# esp_car.net
KiCad netlist of a schematic drawn in EAGLE
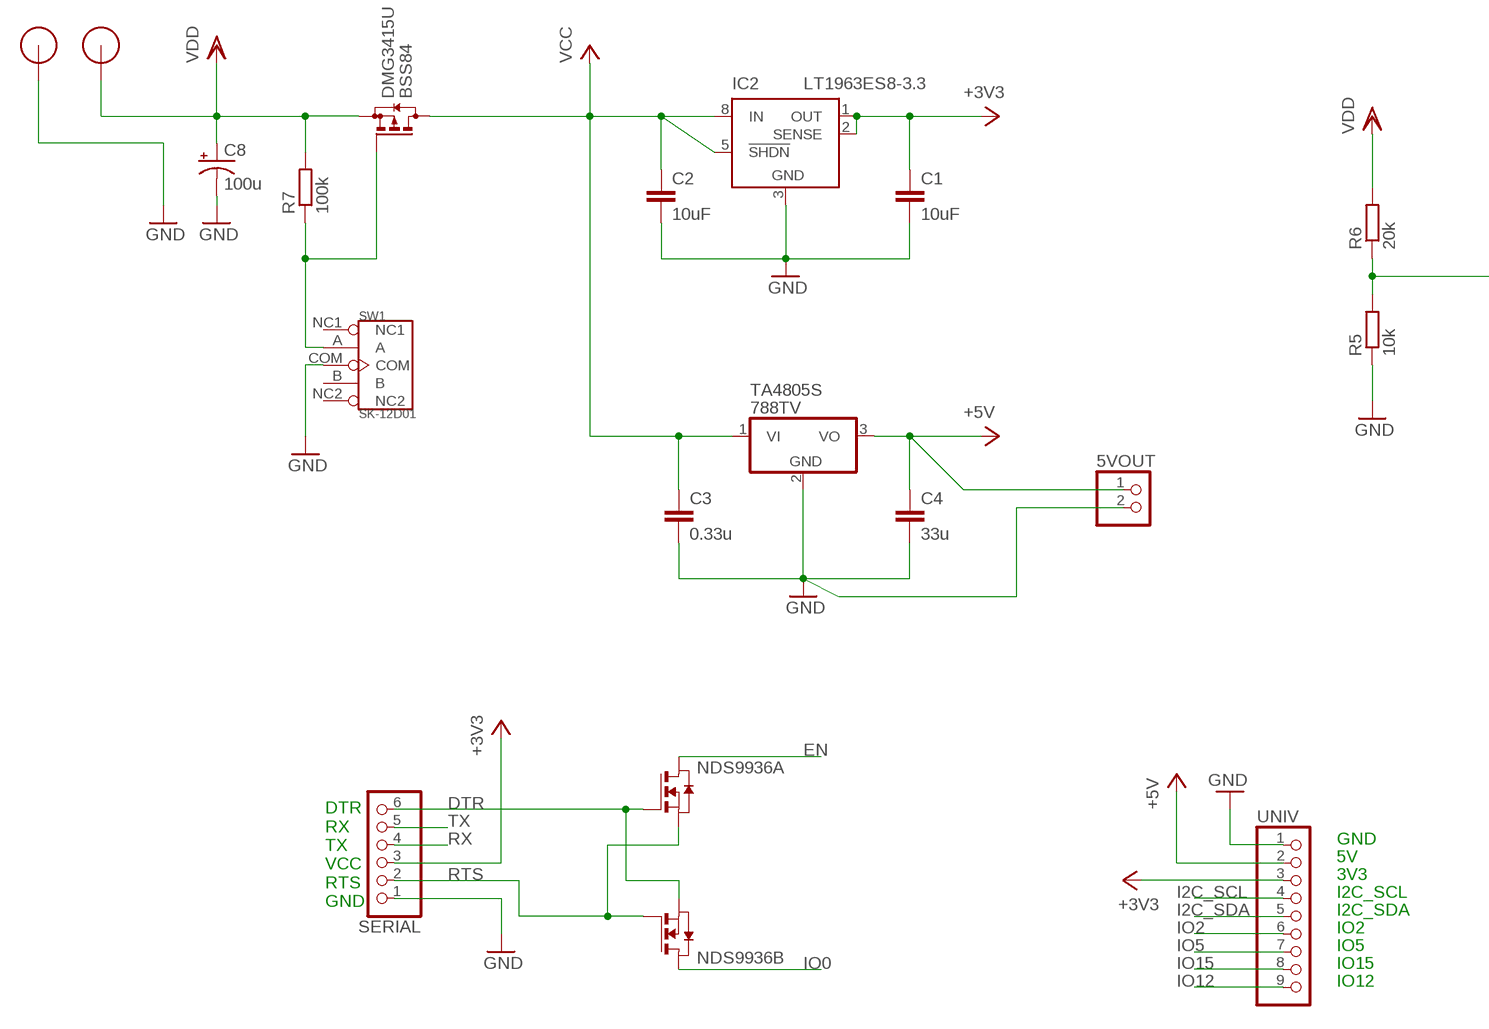
[diagram p0: schematic, sheet 1, part 1 of 2]
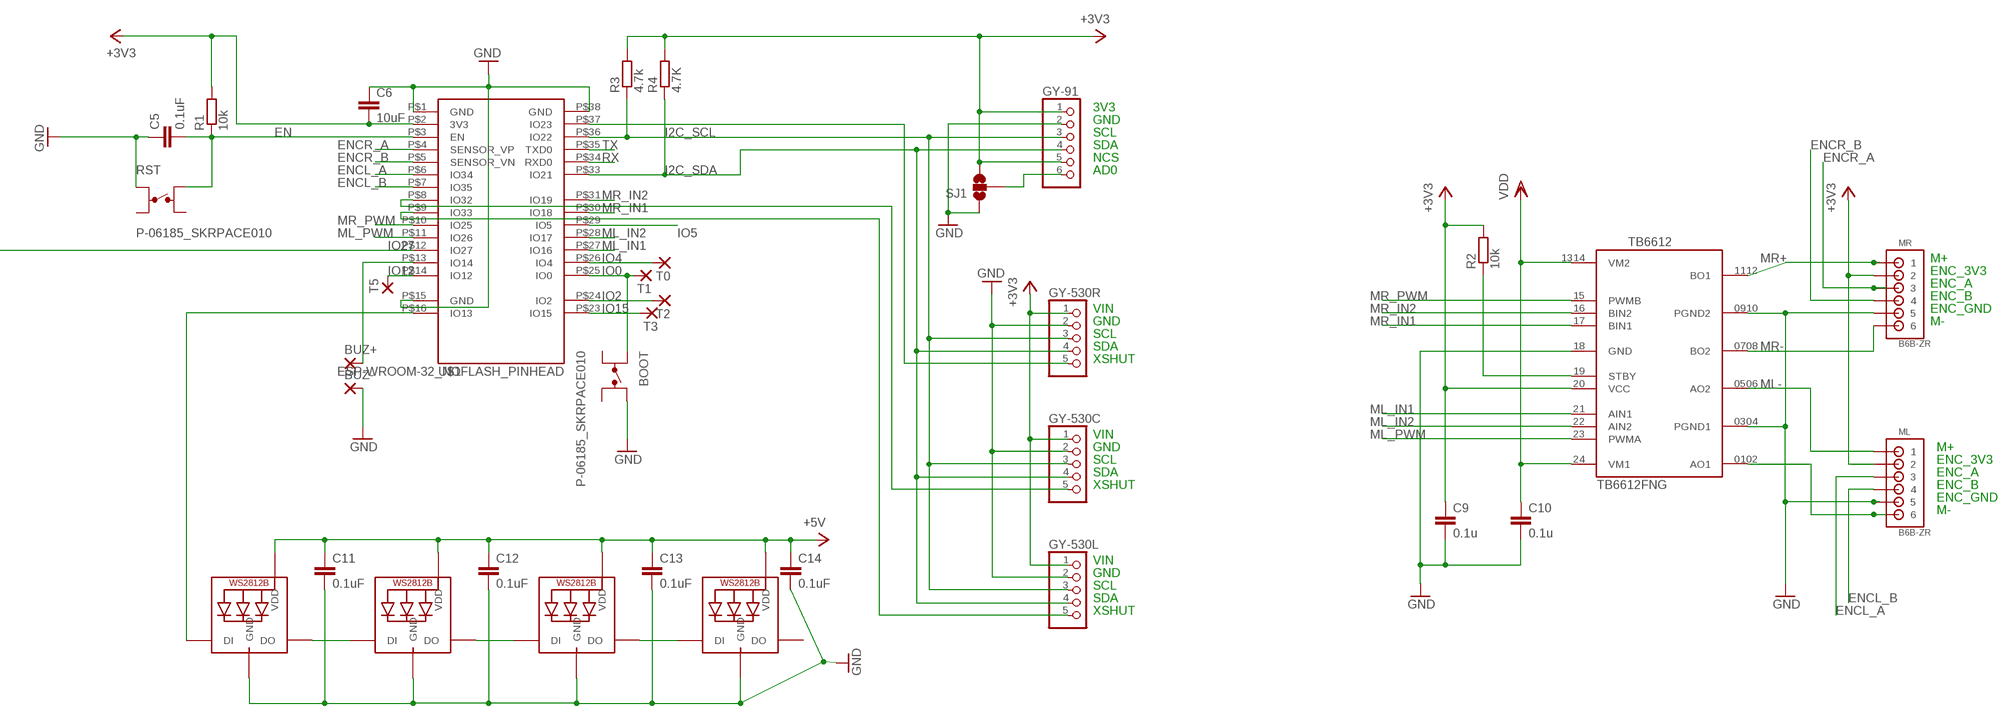
[diagram p1: schematic, sheet 1, part 2 of 2]

(export (version "E")
  (design (tool "Eeschema 10.0.6"))
  (components
    (comp (ref "5VOUT")
      (value "PINHD-1X2")
      (footprint "eagle-import:1X02")
      (libsource (lib "eagle-import") (part "PINHD-1X2"))
    )
    (comp (ref "BOOT")
      (value "P-06185_SKRPACE010")
      (footprint "eagle-import:SKRP")
      (libsource (lib "eagle-import") (part "P-06185_SKRPACE010"))
    )
    (comp (ref "BUZ+")
      (value "SMD2")
      (footprint "eagle-import:SMD1,27-2,54")
      (libsource (lib "eagle-import") (part "SMD2"))
    )
    (comp (ref "BUZ-")
      (value "SMD2")
      (footprint "eagle-import:SMD1,27-2,54")
      (libsource (lib "eagle-import") (part "SMD2"))
    )
    (comp (ref "C1")
      (value "10uF")
      (footprint "eagle-import:C1608")
      (libsource (lib "eagle-import") (part "C-EUC1608"))
    )
    (comp (ref "C2")
      (value "10uF")
      (footprint "eagle-import:C1608")
      (libsource (lib "eagle-import") (part "C-EUC1608"))
    )
    (comp (ref "C3")
      (value "0.33u")
      (footprint "eagle-import:C1608")
      (libsource (lib "eagle-import") (part "C-EUC1608"))
    )
    (comp (ref "C4")
      (value "33u")
      (footprint "eagle-import:C3225")
      (libsource (lib "eagle-import") (part "C-EUC3225"))
    )
    (comp (ref "C5")
      (value "0.1uF")
      (footprint "eagle-import:C1608")
      (libsource (lib "eagle-import") (part "C-EUC1608"))
    )
    (comp (ref "C6")
      (value "10uF")
      (footprint "eagle-import:C1608")
      (libsource (lib "eagle-import") (part "C-EUC1608"))
    )
    (comp (ref "C8")
      (value "100u")
      (footprint "eagle-import:E2,5-6")
      (libsource (lib "eagle-import") (part "CPOL-USE2.5-6"))
    )
    (comp (ref "C9")
      (value "0.1u")
      (footprint "eagle-import:C1608")
      (libsource (lib "eagle-import") (part "C-EUC1608"))
    )
    (comp (ref "C10")
      (value "0.1u")
      (footprint "eagle-import:C1608")
      (libsource (lib "eagle-import") (part "C-EUC1608"))
    )
    (comp (ref "C11")
      (value "0.1uF")
      (footprint "eagle-import:C1608")
      (libsource (lib "eagle-import") (part "C-EUC1608"))
    )
    (comp (ref "C12")
      (value "0.1uF")
      (footprint "eagle-import:C1608")
      (libsource (lib "eagle-import") (part "C-EUC1608"))
    )
    (comp (ref "C13")
      (value "0.1uF")
      (footprint "eagle-import:C1608")
      (libsource (lib "eagle-import") (part "C-EUC1608"))
    )
    (comp (ref "C14")
      (value "0.1uF")
      (footprint "eagle-import:C1608")
      (libsource (lib "eagle-import") (part "C-EUC1608"))
    )
    (comp (ref "DMG3415U")
      (value "BSS84")
      (footprint "eagle-import:SOT23")
      (libsource (lib "eagle-import") (part "BSS84"))
    )
    (comp (ref "GY-91")
      (value "PINHD-1X6")
      (footprint "eagle-import:1X06")
      (libsource (lib "eagle-import") (part "PINHD-1X6"))
    )
    (comp (ref "GY-530C")
      (value "PINHD-1X5")
      (footprint "eagle-import:1X05")
      (libsource (lib "eagle-import") (part "PINHD-1X5"))
    )
    (comp (ref "GY-530L")
      (value "PINHD-1X5")
      (footprint "eagle-import:1X05")
      (libsource (lib "eagle-import") (part "PINHD-1X5"))
    )
    (comp (ref "GY-530R")
      (value "PINHD-1X5")
      (footprint "eagle-import:1X05")
      (libsource (lib "eagle-import") (part "PINHD-1X5"))
    )
    (comp (ref "IC2")
      (value "LT1963ES8-3.3")
      (footprint "eagle-import:SOIC8")
      (libsource (lib "eagle-import") (part "LT1963ES8-3.3"))
    )
    (comp (ref "LED_FL")
      (value "WS2812B5050")
      (footprint "eagle-import:WS2812B")
      (libsource (lib "eagle-import") (part "WS2812B5050"))
    )
    (comp (ref "LED_FR")
      (value "WS2812B5050")
      (footprint "eagle-import:WS2812B")
      (libsource (lib "eagle-import") (part "WS2812B5050"))
    )
    (comp (ref "LED_RL")
      (value "WS2812B5050")
      (footprint "eagle-import:WS2812B")
      (libsource (lib "eagle-import") (part "WS2812B5050"))
    )
    (comp (ref "LED_RR")
      (value "WS2812B5050")
      (footprint "eagle-import:WS2812B")
      (libsource (lib "eagle-import") (part "WS2812B5050"))
    )
    (comp (ref "ML")
      (value "B6B-ZR")
      (footprint "eagle-import:B6B-ZR")
      (libsource (lib "eagle-import") (part "B6B-ZR"))
    )
    (comp (ref "MR")
      (value "B6B-ZR")
      (footprint "eagle-import:B6B-ZR")
      (libsource (lib "eagle-import") (part "B6B-ZR"))
    )
    (comp (ref "NDS9936")
      (value "NMOS2SO8")
      (footprint "eagle-import:SO8")
      (libsource (lib "eagle-import") (part "NMOS2SO8"))
    )
    (comp (ref "R1")
      (value "10k")
      (footprint "eagle-import:R0603")
      (libsource (lib "eagle-import") (part "R-EU_R0603"))
    )
    (comp (ref "R2")
      (value "10k")
      (footprint "eagle-import:R0603")
      (libsource (lib "eagle-import") (part "R-EU_R0603"))
    )
    (comp (ref "R3")
      (value "4.7k")
      (footprint "eagle-import:R0603")
      (libsource (lib "eagle-import") (part "R-EU_R0603"))
    )
    (comp (ref "R4")
      (value "4.7K")
      (footprint "eagle-import:R0603")
      (libsource (lib "eagle-import") (part "R-EU_R0603"))
    )
    (comp (ref "R5")
      (value "10k")
      (footprint "eagle-import:R0603")
      (libsource (lib "eagle-import") (part "R-EU_R0603"))
    )
    (comp (ref "R6")
      (value "20k")
      (footprint "eagle-import:R0603")
      (libsource (lib "eagle-import") (part "R-EU_R0603"))
    )
    (comp (ref "R7")
      (value "100k")
      (footprint "eagle-import:R0603")
      (libsource (lib "eagle-import") (part "R-EU_R0603"))
    )
    (comp (ref "RST")
      (value "P-06185_SKRPACE010")
      (footprint "eagle-import:SKRP")
      (libsource (lib "eagle-import") (part "P-06185_SKRPACE010"))
    )
    (comp (ref "SERIAL")
      (value "PINHD-1X6")
      (footprint "eagle-import:1X06")
      (libsource (lib "eagle-import") (part "PINHD-1X6"))
    )
    (comp (ref "SJ1")
      (value "SOLDERJUMPER_2WAYS")
      (footprint "eagle-import:SJ_3")
      (libsource (lib "eagle-import") (part "SOLDERJUMPER_2WAYS"))
    )
    (comp (ref "SW1")
      (value "SK-12D01")
      (footprint "eagle-import:SW5-2.0-8.8X4.4X4.7MM-90D")
      (libsource (lib "eagle-import") (part "DIP-TOGGLE-SWITCH-ON-ON(3+2P-8.8X4.6MM)"))
    )
    (comp (ref "T0")
      (value "SMD5")
      (footprint "eagle-import:SMD2,54-5,08")
      (libsource (lib "eagle-import") (part "SMD5"))
    )
    (comp (ref "T1")
      (value "SMD5")
      (footprint "eagle-import:SMD2,54-5,08")
      (libsource (lib "eagle-import") (part "SMD5"))
    )
    (comp (ref "T2")
      (value "SMD5")
      (footprint "eagle-import:SMD2,54-5,08")
      (libsource (lib "eagle-import") (part "SMD5"))
    )
    (comp (ref "T3")
      (value "SMD5")
      (footprint "eagle-import:SMD2,54-5,08")
      (libsource (lib "eagle-import") (part "SMD5"))
    )
    (comp (ref "T5")
      (value "SMD5")
      (footprint "eagle-import:SMD2,54-5,08")
      (libsource (lib "eagle-import") (part "SMD5"))
    )
    (comp (ref "TA4805S")
      (value "788TV")
      (footprint "eagle-import:TO220V")
      (libsource (lib "eagle-import") (part "78TV8"))
    )
    (comp (ref "TB6612")
      (value "TB6612_NEW")
      (footprint "eagle-import:SSOP24_TB6612")
      (libsource (lib "eagle-import") (part "TB6612_NEW"))
    )
    (comp (ref "U$1")
      (value "ESP-WROOM-32_NOFLASH_PINHEAD")
      (footprint "eagle-import:ESP-WROOM-32_NOFLASH_PINHEAD")
      (libsource (lib "eagle-import") (part "ESP-WROOM-32_NOFLASH_PINHEAD"))
    )
    (comp (ref "U$5")
      (value "2.0")
      (footprint "eagle-import:2.0")
      (libsource (lib "eagle-import") (part "2.0"))
    )
    (comp (ref "U$7")
      (value "2.0")
      (footprint "eagle-import:2.0")
      (libsource (lib "eagle-import") (part "2.0"))
    )
    (comp (ref "UNIV")
      (value "PINHD-1X9")
      (footprint "eagle-import:1X09-BIG")
      (libsource (lib "eagle-import") (part "PINHD-1X9"))
    )
  )
  (nets
    (net (code "1") (name "+3V3") (class "Default")
      (node (ref "C1") (pin "1") (pinfunction "1_1") (pintype "passive"))
      (node (ref "C6") (pin "2") (pinfunction "2_2") (pintype "passive"))
      (node (ref "C9") (pin "1") (pinfunction "1_1") (pintype "passive"))
      (node (ref "GY-530C") (pin "1") (pinfunction "1_1") (pintype "passive"))
      (node (ref "GY-530L") (pin "1") (pinfunction "1_1") (pintype "passive"))
      (node (ref "GY-530R") (pin "1") (pinfunction "1_1") (pintype "passive"))
      (node (ref "GY-91") (pin "1") (pinfunction "1_1") (pintype "passive"))
      (node (ref "GY-91") (pin "5") (pinfunction "5_5") (pintype "passive"))
      (node (ref "IC2") (pin "1") (pinfunction "OUT_1") (pintype "output"))
      (node (ref "IC2") (pin "2") (pinfunction "SENSE_2") (pintype "input"))
      (node (ref "ML") (pin "2") (pinfunction "2_2") (pintype "bidirectional"))
      (node (ref "MR") (pin "2") (pinfunction "2_2") (pintype "bidirectional"))
      (node (ref "R1") (pin "2") (pinfunction "2_2") (pintype "passive"))
      (node (ref "R2") (pin "2") (pinfunction "2_2") (pintype "passive"))
      (node (ref "R3") (pin "2") (pinfunction "2_2") (pintype "passive"))
      (node (ref "R4") (pin "2") (pinfunction "2_2") (pintype "passive"))
      (node (ref "SERIAL") (pin "3") (pinfunction "3_3") (pintype "passive"))
      (node (ref "SJ1") (pin "3") (pinfunction "3_3") (pintype "passive"))
      (node (ref "TB6612") (pin "20") (pinfunction "VCC_20") (pintype "power_in"))
      (node (ref "U$1") (pin "P$2") (pinfunction "3V3_P$2") (pintype "power_in"))
      (node (ref "UNIV") (pin "3") (pinfunction "3_3") (pintype "passive"))
    )
    (net (code "2") (name "+5V") (class "Default")
      (node (ref "5VOUT") (pin "1") (pinfunction "1_1") (pintype "passive"))
      (node (ref "C11") (pin "1") (pinfunction "1_1") (pintype "passive"))
      (node (ref "C12") (pin "1") (pinfunction "1_1") (pintype "passive"))
      (node (ref "C13") (pin "1") (pinfunction "1_1") (pintype "passive"))
      (node (ref "C14") (pin "1") (pinfunction "1_1") (pintype "passive"))
      (node (ref "C4") (pin "1") (pinfunction "1_1") (pintype "passive"))
      (node (ref "LED_FL") (pin "1-VDD") (pinfunction "VDD_1-VDD") (pintype "power_in"))
      (node (ref "LED_FR") (pin "1-VDD") (pinfunction "VDD_1-VDD") (pintype "power_in"))
      (node (ref "LED_RL") (pin "1-VDD") (pinfunction "VDD_1-VDD") (pintype "power_in"))
      (node (ref "LED_RR") (pin "1-VDD") (pinfunction "VDD_1-VDD") (pintype "power_in"))
      (node (ref "TA4805S") (pin "3") (pinfunction "VO_3") (pintype "passive"))
      (node (ref "UNIV") (pin "2") (pinfunction "2_2") (pintype "passive"))
    )
    (net (code "3") (name "/DTR") (class "Default")
      (node (ref "NDS9936") (pin "2") (pinfunction "G_2") (pintype "passive"))
      (node (ref "NDS9936") (pin "3") (pinfunction "S_3") (pintype "passive"))
      (node (ref "SERIAL") (pin "6") (pinfunction "6_6") (pintype "passive"))
    )
    (net (code "4") (name "/EN") (class "Default")
      (node (ref "C5") (pin "2") (pinfunction "2_2") (pintype "passive"))
      (node (ref "NDS9936") (pin "7") (pinfunction "D_7") (pintype "passive"))
      (node (ref "NDS9936") (pin "8") (pinfunction "D_8") (pintype "passive"))
      (node (ref "R1") (pin "1") (pinfunction "1_1") (pintype "passive"))
      (node (ref "RST") (pin "2A") (pinfunction "P$2A_2A") (pintype "bidirectional"))
      (node (ref "U$1") (pin "P$3") (pinfunction "EN_P$3") (pintype "input"))
    )
    (net (code "5") (name "/ENCL_A") (class "Default")
      (node (ref "ML") (pin "3") (pinfunction "3_3") (pintype "bidirectional"))
      (node (ref "U$1") (pin "P$6") (pinfunction "IO34_P$6") (pintype "bidirectional"))
    )
    (net (code "6") (name "/ENCL_B") (class "Default")
      (node (ref "ML") (pin "4") (pinfunction "4_4") (pintype "bidirectional"))
      (node (ref "U$1") (pin "P$7") (pinfunction "IO35_P$7") (pintype "bidirectional"))
    )
    (net (code "7") (name "/ENCR_A") (class "Default")
      (node (ref "MR") (pin "3") (pinfunction "3_3") (pintype "bidirectional"))
      (node (ref "U$1") (pin "P$4") (pinfunction "SENSOR_VP_P$4") (pintype "bidirectional"))
    )
    (net (code "8") (name "/ENCR_B") (class "Default")
      (node (ref "MR") (pin "4") (pinfunction "4_4") (pintype "bidirectional"))
      (node (ref "U$1") (pin "P$5") (pinfunction "SENSOR_VN_P$5") (pintype "bidirectional"))
    )
    (net (code "9") (name "/I2C_SCL") (class "Default")
      (node (ref "GY-530C") (pin "3") (pinfunction "3_3") (pintype "passive"))
      (node (ref "GY-530L") (pin "3") (pinfunction "3_3") (pintype "passive"))
      (node (ref "GY-530R") (pin "3") (pinfunction "3_3") (pintype "passive"))
      (node (ref "GY-91") (pin "3") (pinfunction "3_3") (pintype "passive"))
      (node (ref "R3") (pin "1") (pinfunction "1_1") (pintype "passive"))
      (node (ref "U$1") (pin "P$36") (pinfunction "IO22_P$36") (pintype "bidirectional"))
      (node (ref "UNIV") (pin "4") (pinfunction "4_4") (pintype "passive"))
    )
    (net (code "10") (name "/I2C_SDA") (class "Default")
      (node (ref "GY-530C") (pin "4") (pinfunction "4_4") (pintype "passive"))
      (node (ref "GY-530L") (pin "4") (pinfunction "4_4") (pintype "passive"))
      (node (ref "GY-530R") (pin "4") (pinfunction "4_4") (pintype "passive"))
      (node (ref "GY-91") (pin "4") (pinfunction "4_4") (pintype "passive"))
      (node (ref "R4") (pin "1") (pinfunction "1_1") (pintype "passive"))
      (node (ref "U$1") (pin "P$33") (pinfunction "IO21_P$33") (pintype "bidirectional"))
      (node (ref "UNIV") (pin "5") (pinfunction "5_5") (pintype "passive"))
    )
    (net (code "11") (name "/IO0") (class "Default")
      (node (ref "BOOT") (pin "1A") (pinfunction "P$1A_1A") (pintype "bidirectional"))
      (node (ref "NDS9936") (pin "5") (pinfunction "D_5") (pintype "passive"))
      (node (ref "NDS9936") (pin "6") (pinfunction "D_6") (pintype "passive"))
      (node (ref "T1") (pin "1") (pinfunction "P_1") (pintype "passive"))
      (node (ref "U$1") (pin "P$25") (pinfunction "IO0_P$25") (pintype "bidirectional"))
    )
    (net (code "12") (name "/IO2") (class "Default")
      (node (ref "T2") (pin "1") (pinfunction "P_1") (pintype "passive"))
      (node (ref "U$1") (pin "P$24") (pinfunction "IO2_P$24") (pintype "bidirectional"))
      (node (ref "UNIV") (pin "6") (pinfunction "6_6") (pintype "passive"))
    )
    (net (code "13") (name "/IO4") (class "Default")
      (node (ref "T0") (pin "1") (pinfunction "P_1") (pintype "passive"))
      (node (ref "U$1") (pin "P$26") (pinfunction "IO4_P$26") (pintype "bidirectional"))
    )
    (net (code "14") (name "/IO5") (class "Default")
      (node (ref "U$1") (pin "P$29") (pinfunction "IO5_P$29") (pintype "bidirectional"))
      (node (ref "UNIV") (pin "7") (pinfunction "7_7") (pintype "passive"))
    )
    (net (code "15") (name "/IO12") (class "Default")
      (node (ref "T5") (pin "1") (pinfunction "P_1") (pintype "passive"))
      (node (ref "U$1") (pin "P$14") (pinfunction "IO12_P$14") (pintype "bidirectional"))
      (node (ref "UNIV") (pin "9") (pinfunction "9_9") (pintype "passive"))
    )
    (net (code "16") (name "/IO15") (class "Default")
      (node (ref "T3") (pin "1") (pinfunction "P_1") (pintype "passive"))
      (node (ref "U$1") (pin "P$23") (pinfunction "IO15_P$23") (pintype "bidirectional"))
      (node (ref "UNIV") (pin "8") (pinfunction "8_8") (pintype "passive"))
    )
    (net (code "17") (name "/IO27") (class "Default")
      (node (ref "R5") (pin "2") (pinfunction "2_2") (pintype "passive"))
      (node (ref "R6") (pin "1") (pinfunction "1_1") (pintype "passive"))
      (node (ref "U$1") (pin "P$12") (pinfunction "IO27_P$12") (pintype "bidirectional"))
    )
    (net (code "18") (name "/ML-") (class "Default")
      (node (ref "ML") (pin "6") (pinfunction "6_6") (pintype "bidirectional"))
      (node (ref "TB6612") (pin "0102") (pinfunction "AO1_0102") (pintype "output"))
    )
    (net (code "19") (name "/ML_IN1") (class "Default")
      (node (ref "TB6612") (pin "21") (pinfunction "AIN1_21") (pintype "input"))
      (node (ref "U$1") (pin "P$27") (pinfunction "IO16_P$27") (pintype "bidirectional"))
    )
    (net (code "20") (name "/ML_IN2") (class "Default")
      (node (ref "TB6612") (pin "22") (pinfunction "AIN2_22") (pintype "input"))
      (node (ref "U$1") (pin "P$28") (pinfunction "IO17_P$28") (pintype "bidirectional"))
    )
    (net (code "21") (name "/ML_PWM") (class "Default")
      (node (ref "TB6612") (pin "23") (pinfunction "PWMA_23") (pintype "input"))
      (node (ref "U$1") (pin "P$11") (pinfunction "IO26_P$11") (pintype "bidirectional"))
    )
    (net (code "22") (name "/MR+") (class "Default")
      (node (ref "MR") (pin "1") (pinfunction "1_1") (pintype "bidirectional"))
      (node (ref "TB6612") (pin "1112") (pinfunction "BO1_1112") (pintype "output"))
    )
    (net (code "23") (name "/MR-") (class "Default")
      (node (ref "MR") (pin "6") (pinfunction "6_6") (pintype "bidirectional"))
      (node (ref "TB6612") (pin "0708") (pinfunction "BO2_0708") (pintype "output"))
    )
    (net (code "24") (name "/MR_IN1") (class "Default")
      (node (ref "TB6612") (pin "17") (pinfunction "BIN1_17") (pintype "input"))
      (node (ref "U$1") (pin "P$30") (pinfunction "IO18_P$30") (pintype "bidirectional"))
    )
    (net (code "25") (name "/MR_IN2") (class "Default")
      (node (ref "TB6612") (pin "16") (pinfunction "BIN2_16") (pintype "input"))
      (node (ref "U$1") (pin "P$31") (pinfunction "IO19_P$31") (pintype "bidirectional"))
    )
    (net (code "26") (name "/MR_PWM") (class "Default")
      (node (ref "TB6612") (pin "15") (pinfunction "PWMB_15") (pintype "input"))
      (node (ref "U$1") (pin "P$10") (pinfunction "IO25_P$10") (pintype "bidirectional"))
    )
    (net (code "27") (name "/RTS") (class "Default")
      (node (ref "NDS9936") (pin "1") (pinfunction "S_1") (pintype "passive"))
      (node (ref "NDS9936") (pin "4") (pinfunction "G_4") (pintype "passive"))
      (node (ref "SERIAL") (pin "2") (pinfunction "2_2") (pintype "passive"))
    )
    (net (code "28") (name "/RX") (class "Default")
      (node (ref "SERIAL") (pin "4") (pinfunction "4_4") (pintype "passive"))
      (node (ref "U$1") (pin "P$34") (pinfunction "RXD0_P$34") (pintype "bidirectional"))
    )
    (net (code "29") (name "/TX") (class "Default")
      (node (ref "SERIAL") (pin "5") (pinfunction "5_5") (pintype "passive"))
      (node (ref "U$1") (pin "P$35") (pinfunction "TXD0_P$35") (pintype "bidirectional"))
    )
    (net (code "30") (name "GND") (class "Default")
      (node (ref "5VOUT") (pin "2") (pinfunction "2_2") (pintype "passive"))
      (node (ref "BOOT") (pin "2A") (pinfunction "P$2A_2A") (pintype "bidirectional"))
      (node (ref "BUZ-") (pin "1") (pinfunction "P_1") (pintype "passive"))
      (node (ref "C1") (pin "2") (pinfunction "2_2") (pintype "passive"))
      (node (ref "C10") (pin "2") (pinfunction "2_2") (pintype "passive"))
      (node (ref "C11") (pin "2") (pinfunction "2_2") (pintype "passive"))
      (node (ref "C12") (pin "2") (pinfunction "2_2") (pintype "passive"))
      (node (ref "C13") (pin "2") (pinfunction "2_2") (pintype "passive"))
      (node (ref "C14") (pin "2") (pinfunction "2_2") (pintype "passive"))
      (node (ref "C2") (pin "2") (pinfunction "2_2") (pintype "passive"))
      (node (ref "C3") (pin "2") (pinfunction "2_2") (pintype "passive"))
      (node (ref "C4") (pin "2") (pinfunction "2_2") (pintype "passive"))
      (node (ref "C5") (pin "1") (pinfunction "1_1") (pintype "passive"))
      (node (ref "C6") (pin "1") (pinfunction "1_1") (pintype "passive"))
      (node (ref "C8") (pin "-") (pinfunction "-_-") (pintype "passive"))
      (node (ref "C9") (pin "2") (pinfunction "2_2") (pintype "passive"))
      (node (ref "GY-530C") (pin "2") (pinfunction "2_2") (pintype "passive"))
      (node (ref "GY-530L") (pin "2") (pinfunction "2_2") (pintype "passive"))
      (node (ref "GY-530R") (pin "2") (pinfunction "2_2") (pintype "passive"))
      (node (ref "GY-91") (pin "2") (pinfunction "2_2") (pintype "passive"))
      (node (ref "IC2") (pin "3") (pinfunction "GND_3") (pintype "power_in"))
      (node (ref "LED_FL") (pin "3-GND") (pinfunction "GND_3-GND") (pintype "power_in"))
      (node (ref "LED_FR") (pin "3-GND") (pinfunction "GND_3-GND") (pintype "power_in"))
      (node (ref "LED_RL") (pin "3-GND") (pinfunction "GND_3-GND") (pintype "power_in"))
      (node (ref "LED_RR") (pin "3-GND") (pinfunction "GND_3-GND") (pintype "power_in"))
      (node (ref "ML") (pin "5") (pinfunction "5_5") (pintype "bidirectional"))
      (node (ref "MR") (pin "5") (pinfunction "5_5") (pintype "bidirectional"))
      (node (ref "R5") (pin "1") (pinfunction "1_1") (pintype "passive"))
      (node (ref "RST") (pin "1A") (pinfunction "P$1A_1A") (pintype "bidirectional"))
      (node (ref "SERIAL") (pin "1") (pinfunction "1_1") (pintype "passive"))
      (node (ref "SJ1") (pin "1") (pinfunction "1_1") (pintype "passive"))
      (node (ref "SW1") (pin "COM") (pinfunction "COM_COM") (pintype "bidirectional"))
      (node (ref "TA4805S") (pin "2") (pinfunction "GND_2") (pintype "passive"))
      (node (ref "TB6612") (pin "0304") (pinfunction "PGND1_0304") (pintype "power_in"))
      (node (ref "TB6612") (pin "0910") (pinfunction "PGND2_0910") (pintype "power_in"))
      (node (ref "TB6612") (pin "18") (pinfunction "GND_18") (pintype "power_in"))
      (node (ref "U$1") (pin "P$1") (pinfunction "GND_P$1") (pintype "power_in"))
      (node (ref "U$1") (pin "P$15") (pinfunction "GND_P$15") (pintype "power_in"))
      (node (ref "U$1") (pin "P$38") (pinfunction "GND_P$38") (pintype "power_in"))
      (node (ref "U$5") (pin "P$1") (pinfunction "P$1_P$1") (pintype "bidirectional"))
      (node (ref "UNIV") (pin "1") (pinfunction "1_1") (pintype "passive"))
    )
    (net (code "31") (name "Net-(BUZ+-P)") (class "Default")
      (node (ref "BUZ+") (pin "1") (pinfunction "P_1") (pintype "passive"))
      (node (ref "U$1") (pin "P$13") (pinfunction "IO14_P$13") (pintype "bidirectional"))
    )
    (net (code "32") (name "Net-(DMG3415U-G)") (class "Default")
      (node (ref "DMG3415U") (pin "1") (pinfunction "G_1") (pintype "passive"))
      (node (ref "R7") (pin "1") (pinfunction "1_1") (pintype "passive"))
      (node (ref "SW1") (pin "A") (pinfunction "A_A") (pintype "bidirectional"))
    )
    (net (code "33") (name "Net-(GY-91-Pad6)") (class "Default")
      (node (ref "GY-91") (pin "6") (pinfunction "6_6") (pintype "passive"))
      (node (ref "SJ1") (pin "2") (pinfunction "2_2") (pintype "passive"))
    )
    (net (code "34") (name "Net-(LED_FL-DI)") (class "Default")
      (node (ref "LED_FL") (pin "4-DIN") (pinfunction "DI_4-DIN") (pintype "input"))
      (node (ref "U$1") (pin "P$16") (pinfunction "IO13_P$16") (pintype "bidirectional"))
    )
    (net (code "35") (name "Net-(LED_FL-DO)") (class "Default")
      (node (ref "LED_FL") (pin "2-DOUT") (pinfunction "DO_2-DOUT") (pintype "output"))
      (node (ref "LED_RL") (pin "4-DIN") (pinfunction "DI_4-DIN") (pintype "input"))
    )
    (net (code "36") (name "Net-(LED_FR-DI)") (class "Default")
      (node (ref "LED_FR") (pin "4-DIN") (pinfunction "DI_4-DIN") (pintype "input"))
      (node (ref "LED_RR") (pin "2-DOUT") (pinfunction "DO_2-DOUT") (pintype "output"))
    )
    (net (code "37") (name "Net-(LED_RL-DO)") (class "Default")
      (node (ref "LED_RL") (pin "2-DOUT") (pinfunction "DO_2-DOUT") (pintype "output"))
      (node (ref "LED_RR") (pin "4-DIN") (pinfunction "DI_4-DIN") (pintype "input"))
    )
    (net (code "38") (name "Net-(TB6612-AO2)") (class "Default")
      (node (ref "ML") (pin "1") (pinfunction "1_1") (pintype "bidirectional"))
      (node (ref "TB6612") (pin "0506") (pinfunction "AO2_0506") (pintype "output"))
    )
    (net (code "39") (name "Net-(TB6612-STBY)") (class "Default")
      (node (ref "R2") (pin "1") (pinfunction "1_1") (pintype "passive"))
      (node (ref "TB6612") (pin "19") (pinfunction "STBY_19") (pintype "input"))
    )
    (net (code "40") (name "Net-(U$1-IO23)") (class "Default")
      (node (ref "GY-530R") (pin "5") (pinfunction "5_5") (pintype "passive"))
      (node (ref "U$1") (pin "P$37") (pinfunction "IO23_P$37") (pintype "bidirectional"))
    )
    (net (code "41") (name "Net-(U$1-IO32)") (class "Default")
      (node (ref "GY-530C") (pin "5") (pinfunction "5_5") (pintype "passive"))
      (node (ref "U$1") (pin "P$8") (pinfunction "IO32_P$8") (pintype "bidirectional"))
    )
    (net (code "42") (name "Net-(U$1-IO33)") (class "Default")
      (node (ref "GY-530L") (pin "5") (pinfunction "5_5") (pintype "passive"))
      (node (ref "U$1") (pin "P$9") (pinfunction "IO33_P$9") (pintype "bidirectional"))
    )
    (net (code "43") (name "VCC") (class "Default")
      (node (ref "C2") (pin "1") (pinfunction "1_1") (pintype "passive"))
      (node (ref "C3") (pin "1") (pinfunction "1_1") (pintype "passive"))
      (node (ref "DMG3415U") (pin "3") (pinfunction "D_3") (pintype "passive"))
      (node (ref "IC2") (pin "5") (pinfunction "~{SHDN}_5") (pintype "input"))
      (node (ref "IC2") (pin "8") (pinfunction "IN_8") (pintype "input"))
      (node (ref "TA4805S") (pin "1") (pinfunction "VI_1") (pintype "input"))
    )
    (net (code "44") (name "VDD") (class "Default")
      (node (ref "C10") (pin "1") (pinfunction "1_1") (pintype "passive"))
      (node (ref "C8") (pin "+") (pinfunction "+_+") (pintype "passive"))
      (node (ref "DMG3415U") (pin "2") (pinfunction "S_2") (pintype "passive"))
      (node (ref "R6") (pin "2") (pinfunction "2_2") (pintype "passive"))
      (node (ref "R7") (pin "2") (pinfunction "2_2") (pintype "passive"))
      (node (ref "TB6612") (pin "1314") (pinfunction "VM2_1314") (pintype "power_in"))
      (node (ref "TB6612") (pin "24") (pinfunction "VM1_24") (pintype "power_in"))
      (node (ref "U$7") (pin "P$1") (pinfunction "P$1_P$1") (pintype "bidirectional"))
    )
    (net (code "45") (name "unconnected-(BOOT-P$1B-Pad1B)") (class "Default")
      (node (ref "BOOT") (pin "1B") (pinfunction "P$1B_1B") (pintype "bidirectional"))
    )
    (net (code "46") (name "unconnected-(BOOT-P$2B-Pad2B)") (class "Default")
      (node (ref "BOOT") (pin "2B") (pinfunction "P$2B_2B") (pintype "bidirectional"))
    )
    (net (code "47") (name "unconnected-(LED_FR-DO-Pad2-DOUT)") (class "Default")
      (node (ref "LED_FR") (pin "2-DOUT") (pinfunction "DO_2-DOUT") (pintype "output"))
    )
    (net (code "48") (name "unconnected-(RST-P$1B-Pad1B)") (class "Default")
      (node (ref "RST") (pin "1B") (pinfunction "P$1B_1B") (pintype "bidirectional"))
    )
    (net (code "49") (name "unconnected-(RST-P$2B-Pad2B)") (class "Default")
      (node (ref "RST") (pin "2B") (pinfunction "P$2B_2B") (pintype "bidirectional"))
    )
    (net (code "50") (name "unconnected-(SW1-PadB)") (class "Default")
      (node (ref "SW1") (pin "B") (pinfunction "B_B") (pintype "bidirectional"))
    )
    (net (code "51") (name "unconnected-(SW1-PadNC1)") (class "Default")
      (node (ref "SW1") (pin "NC1") (pinfunction "NC1_NC1") (pintype "bidirectional"))
    )
    (net (code "52") (name "unconnected-(SW1-PadNC2)") (class "Default")
      (node (ref "SW1") (pin "NC2") (pinfunction "NC2_NC2") (pintype "bidirectional"))
    )
  )
)
